# Turnout_Decoder_V1_1Hall.net
KiCad netlist of a schematic drawn in EAGLE
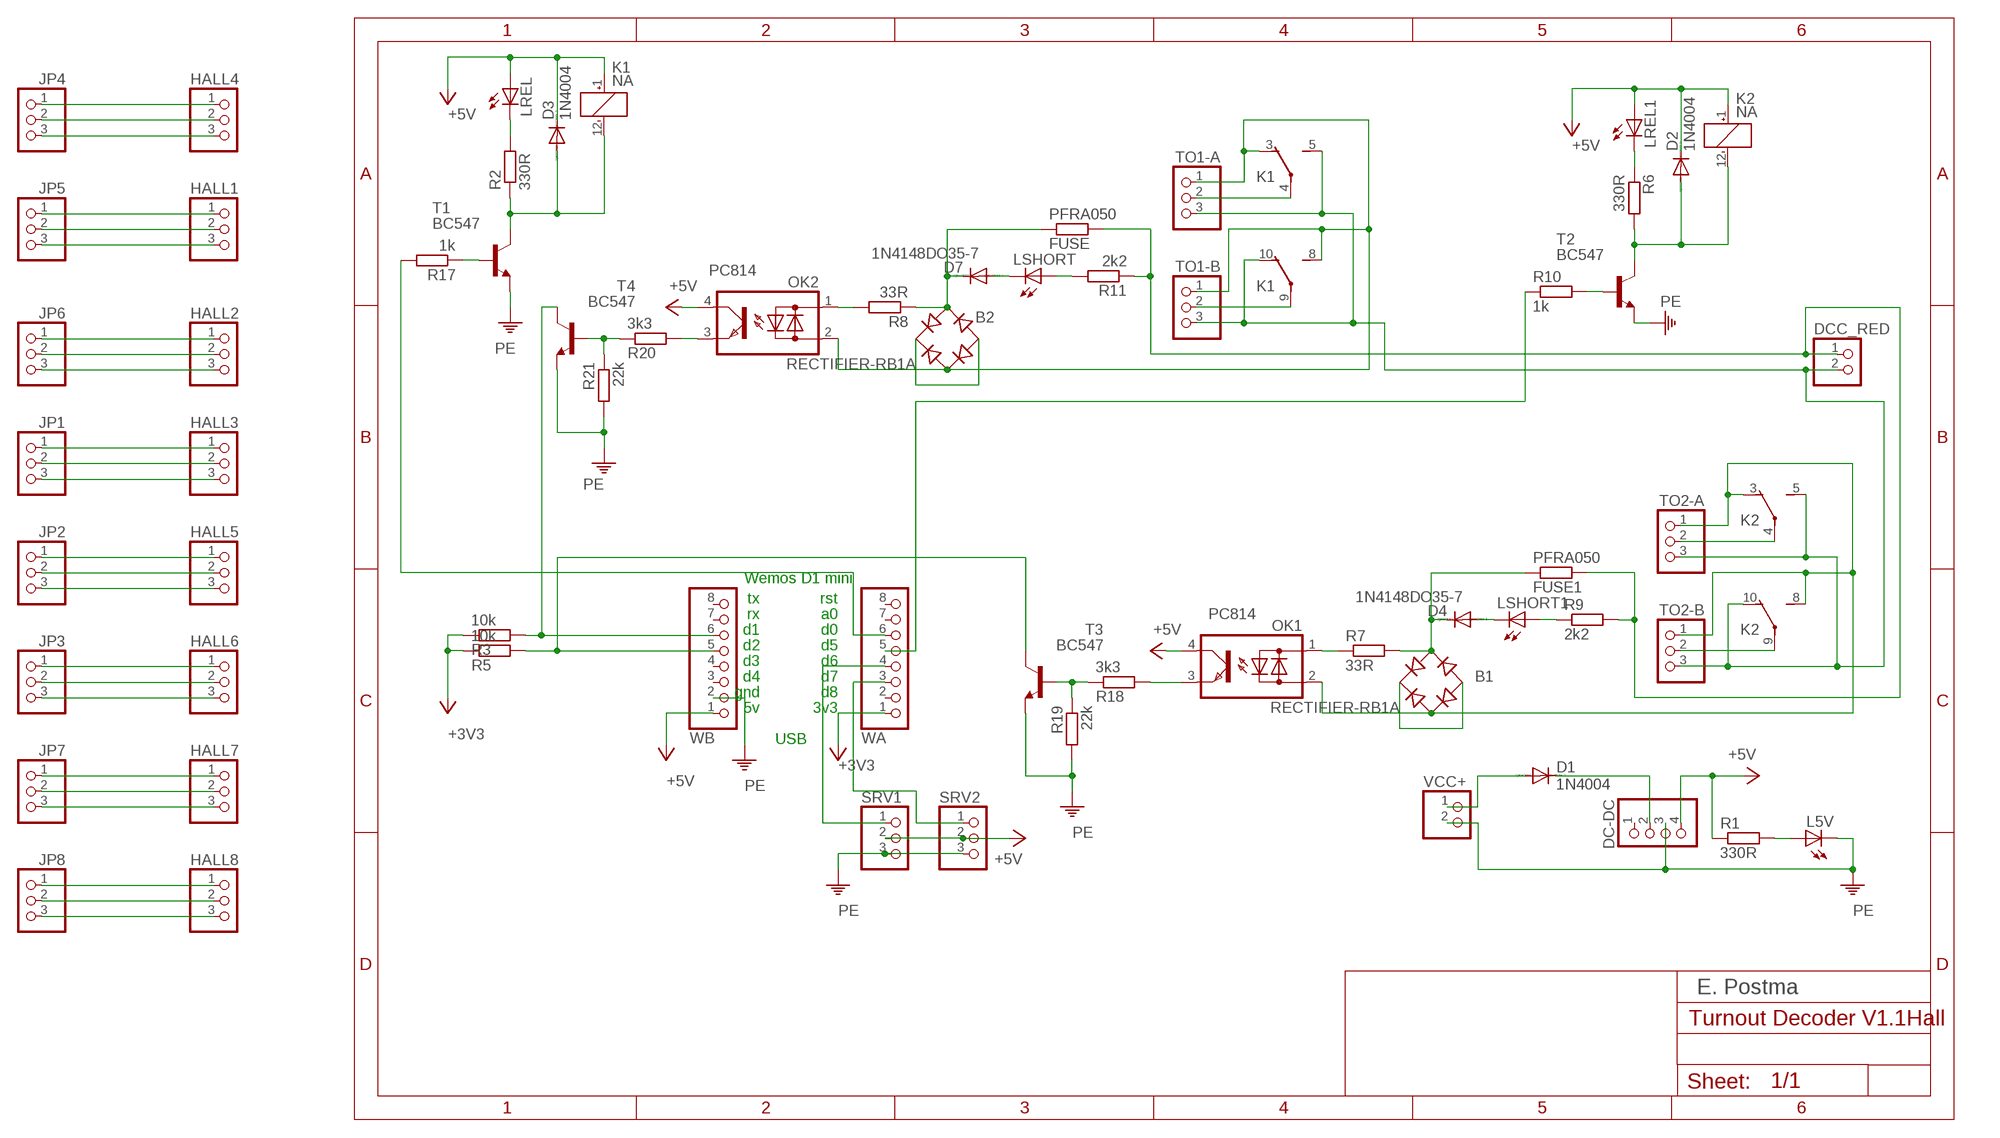
[diagram p0: schematic, sheet 1]

(export (version "E")
  (design (tool "Eeschema 10.0.6"))
  (components
    (comp (ref "B1")
      (value "RECTIFIER-RB1A")
      (footprint "eagle-import:RB1A")
      (libsource (lib "eagle-import") (part "RECTIFIER-RB1A"))
    )
    (comp (ref "B2")
      (value "RECTIFIER-RB1A")
      (footprint "eagle-import:RB1A")
      (libsource (lib "eagle-import") (part "RECTIFIER-RB1A"))
    )
    (comp (ref "D1")
      (value "1N4004")
      (footprint "eagle-import:DO41-10")
      (libsource (lib "eagle-import") (part "1N4004"))
    )
    (comp (ref "D2")
      (value "1N4004")
      (footprint "eagle-import:DO41-10")
      (libsource (lib "eagle-import") (part "1N4004"))
    )
    (comp (ref "D3")
      (value "1N4004")
      (footprint "eagle-import:DO41-10")
      (libsource (lib "eagle-import") (part "1N4004"))
    )
    (comp (ref "D4")
      (value "1N4148DO35-7")
      (footprint "eagle-import:DO35-7")
      (libsource (lib "eagle-import") (part "1N4148DO35-7"))
    )
    (comp (ref "D7")
      (value "1N4148DO35-7")
      (footprint "eagle-import:DO35-7")
      (libsource (lib "eagle-import") (part "1N4148DO35-7"))
    )
    (comp (ref "DC-DC")
      (value "PINHD-1X4")
      (footprint "eagle-import:1X04")
      (libsource (lib "eagle-import") (part "PINHD-1X4"))
    )
    (comp (ref "DCC_RED")
      (value "PINHD-1X2")
      (footprint "eagle-import:1X02")
      (libsource (lib "eagle-import") (part "PINHD-1X2"))
    )
    (comp (ref "FUSE")
      (value "PFRA050")
      (footprint "eagle-import:0414V")
      (libsource (lib "eagle-import") (part "R-EU_0414/5V"))
    )
    (comp (ref "FUSE1")
      (value "PFRA050")
      (footprint "eagle-import:0414V")
      (libsource (lib "eagle-import") (part "R-EU_0414/5V"))
    )
    (comp (ref "HALL1")
      (value "PINHD-1X3")
      (footprint "eagle-import:1X03")
      (libsource (lib "eagle-import") (part "PINHD-1X3"))
    )
    (comp (ref "HALL2")
      (value "PINHD-1X3")
      (footprint "eagle-import:1X03")
      (libsource (lib "eagle-import") (part "PINHD-1X3"))
    )
    (comp (ref "HALL3")
      (value "PINHD-1X3")
      (footprint "eagle-import:1X03")
      (libsource (lib "eagle-import") (part "PINHD-1X3"))
    )
    (comp (ref "HALL4")
      (value "PINHD-1X3")
      (footprint "eagle-import:1X03")
      (libsource (lib "eagle-import") (part "PINHD-1X3"))
    )
    (comp (ref "HALL5")
      (value "PINHD-1X3")
      (footprint "eagle-import:1X03")
      (libsource (lib "eagle-import") (part "PINHD-1X3"))
    )
    (comp (ref "HALL6")
      (value "PINHD-1X3")
      (footprint "eagle-import:1X03")
      (libsource (lib "eagle-import") (part "PINHD-1X3"))
    )
    (comp (ref "HALL7")
      (value "PINHD-1X3")
      (footprint "eagle-import:1X03")
      (libsource (lib "eagle-import") (part "PINHD-1X3"))
    )
    (comp (ref "HALL8")
      (value "PINHD-1X3")
      (footprint "eagle-import:1X03")
      (libsource (lib "eagle-import") (part "PINHD-1X3"))
    )
    (comp (ref "JP1")
      (value "PINHD-1X3")
      (footprint "eagle-import:1X03")
      (libsource (lib "eagle-import") (part "PINHD-1X3"))
    )
    (comp (ref "JP2")
      (value "PINHD-1X3")
      (footprint "eagle-import:1X03")
      (libsource (lib "eagle-import") (part "PINHD-1X3"))
    )
    (comp (ref "JP3")
      (value "PINHD-1X3")
      (footprint "eagle-import:1X03")
      (libsource (lib "eagle-import") (part "PINHD-1X3"))
    )
    (comp (ref "JP4")
      (value "PINHD-1X3")
      (footprint "eagle-import:1X03")
      (libsource (lib "eagle-import") (part "PINHD-1X3"))
    )
    (comp (ref "JP5")
      (value "PINHD-1X3")
      (footprint "eagle-import:1X03")
      (libsource (lib "eagle-import") (part "PINHD-1X3"))
    )
    (comp (ref "JP6")
      (value "PINHD-1X3")
      (footprint "eagle-import:1X03")
      (libsource (lib "eagle-import") (part "PINHD-1X3"))
    )
    (comp (ref "JP7")
      (value "PINHD-1X3")
      (footprint "eagle-import:1X03")
      (libsource (lib "eagle-import") (part "PINHD-1X3"))
    )
    (comp (ref "JP8")
      (value "PINHD-1X3")
      (footprint "eagle-import:1X03")
      (libsource (lib "eagle-import") (part "PINHD-1X3"))
    )
    (comp (ref "K1") (value "NA") (footprint "eagle-import:NA") (libsource (lib "eagle-import") (part "NA")))
    (comp (ref "K2") (value "NA") (footprint "eagle-import:NA") (libsource (lib "eagle-import") (part "NA")))
    (comp (ref "L5V")
      (value "LED3MM")
      (footprint "eagle-import:LED3MM")
      (libsource (lib "eagle-import") (part "LED3MM"))
    )
    (comp (ref "LREL")
      (value "LED3MM")
      (footprint "eagle-import:LED3MM")
      (libsource (lib "eagle-import") (part "LED3MM"))
    )
    (comp (ref "LREL1")
      (value "LED3MM")
      (footprint "eagle-import:LED3MM")
      (libsource (lib "eagle-import") (part "LED3MM"))
    )
    (comp (ref "LSHORT")
      (value "LED3MM")
      (footprint "eagle-import:LED3MM")
      (libsource (lib "eagle-import") (part "LED3MM"))
    )
    (comp (ref "LSHORT1")
      (value "LED3MM")
      (footprint "eagle-import:LED3MM")
      (libsource (lib "eagle-import") (part "LED3MM"))
    )
    (comp (ref "OK1")
      (value "PC814")
      (footprint "eagle-import:DIL04")
      (libsource (lib "eagle-import") (part "PC814"))
    )
    (comp (ref "OK2")
      (value "PC814")
      (footprint "eagle-import:DIL04")
      (libsource (lib "eagle-import") (part "PC814"))
    )
    (comp (ref "R1")
      (value "330R")
      (footprint "eagle-import:0207_7")
      (libsource (lib "eagle-import") (part "resistor_348_R-EU_0207/7"))
    )
    (comp (ref "R2")
      (value "330R")
      (footprint "eagle-import:0207_7")
      (libsource (lib "eagle-import") (part "resistor_348_R-EU_0207/7"))
    )
    (comp (ref "R3")
      (value "10k")
      (footprint "eagle-import:0207_7")
      (libsource (lib "eagle-import") (part "resistor_348_R-EU_0207/7"))
    )
    (comp (ref "R5")
      (value "10k")
      (footprint "eagle-import:0207_7")
      (libsource (lib "eagle-import") (part "resistor_348_R-EU_0207/7"))
    )
    (comp (ref "R6")
      (value "330R")
      (footprint "eagle-import:0207_7")
      (libsource (lib "eagle-import") (part "resistor_348_R-EU_0207/7"))
    )
    (comp (ref "R7")
      (value "33R")
      (footprint "eagle-import:0207_7")
      (libsource (lib "eagle-import") (part "resistor_348_R-EU_0207/7"))
    )
    (comp (ref "R8")
      (value "33R")
      (footprint "eagle-import:0207_7")
      (libsource (lib "eagle-import") (part "resistor_348_R-EU_0207/7"))
    )
    (comp (ref "R9")
      (value "2k2")
      (footprint "eagle-import:0207_7")
      (libsource (lib "eagle-import") (part "resistor_348_R-EU_0207/7"))
    )
    (comp (ref "R10")
      (value "1k")
      (footprint "eagle-import:0207_7")
      (libsource (lib "eagle-import") (part "resistor_348_R-EU_0207/7"))
    )
    (comp (ref "R11")
      (value "2k2")
      (footprint "eagle-import:0207_7")
      (libsource (lib "eagle-import") (part "resistor_348_R-EU_0207/7"))
    )
    (comp (ref "R17")
      (value "1k")
      (footprint "eagle-import:0207_7")
      (libsource (lib "eagle-import") (part "resistor_348_R-EU_0207/7"))
    )
    (comp (ref "R18")
      (value "3k3")
      (footprint "eagle-import:0207_7")
      (libsource (lib "eagle-import") (part "resistor_348_R-EU_0207/7"))
    )
    (comp (ref "R19")
      (value "22k")
      (footprint "eagle-import:0207_7")
      (libsource (lib "eagle-import") (part "resistor_348_R-EU_0207/7"))
    )
    (comp (ref "R20")
      (value "3k3")
      (footprint "eagle-import:0207_7")
      (libsource (lib "eagle-import") (part "resistor_348_R-EU_0207/7"))
    )
    (comp (ref "R21")
      (value "22k")
      (footprint "eagle-import:0207_7")
      (libsource (lib "eagle-import") (part "resistor_348_R-EU_0207/7"))
    )
    (comp (ref "SRV1")
      (value "PINHD-1X3")
      (footprint "eagle-import:1X03")
      (libsource (lib "eagle-import") (part "PINHD-1X3"))
    )
    (comp (ref "SRV2")
      (value "PINHD-1X3")
      (footprint "eagle-import:1X03")
      (libsource (lib "eagle-import") (part "PINHD-1X3"))
    )
    (comp (ref "T1")
      (value "BC547")
      (footprint "eagle-import:TO92")
      (libsource (lib "eagle-import") (part "BC547"))
    )
    (comp (ref "T2")
      (value "BC547")
      (footprint "eagle-import:TO92")
      (libsource (lib "eagle-import") (part "BC547"))
    )
    (comp (ref "T3")
      (value "BC547")
      (footprint "eagle-import:TO92")
      (libsource (lib "eagle-import") (part "BC547"))
    )
    (comp (ref "T4")
      (value "BC547")
      (footprint "eagle-import:TO92")
      (libsource (lib "eagle-import") (part "BC547"))
    )
    (comp (ref "TO1-A")
      (value "PINHD-1X3")
      (footprint "eagle-import:1X03")
      (libsource (lib "eagle-import") (part "PINHD-1X3"))
    )
    (comp (ref "TO1-B")
      (value "PINHD-1X3")
      (footprint "eagle-import:1X03")
      (libsource (lib "eagle-import") (part "PINHD-1X3"))
    )
    (comp (ref "TO2-A")
      (value "PINHD-1X3")
      (footprint "eagle-import:1X03")
      (libsource (lib "eagle-import") (part "PINHD-1X3"))
    )
    (comp (ref "TO2-B")
      (value "PINHD-1X3")
      (footprint "eagle-import:1X03")
      (libsource (lib "eagle-import") (part "PINHD-1X3"))
    )
    (comp (ref "VCC+")
      (value "PINHD-1X2")
      (footprint "eagle-import:1X02")
      (libsource (lib "eagle-import") (part "PINHD-1X2"))
    )
    (comp (ref "WA")
      (value "PINHD-1X8")
      (footprint "eagle-import:1X08")
      (libsource (lib "eagle-import") (part "PINHD-1X8"))
    )
    (comp (ref "WB")
      (value "PINHD-1X8")
      (footprint "eagle-import:1X08")
      (libsource (lib "eagle-import") (part "PINHD-1X8"))
    )
  )
  (nets
    (net (code "1") (name "+3V3") (class "Default")
      (node (ref "R3") (pin "1") (pinfunction "1_1") (pintype "passive"))
      (node (ref "R5") (pin "1") (pinfunction "1_1") (pintype "passive"))
      (node (ref "WA") (pin "1") (pinfunction "1_1") (pintype "passive"))
    )
    (net (code "2") (name "+5V") (class "Default")
      (node (ref "D2") (pin "C") (pinfunction "C_C") (pintype "passive"))
      (node (ref "D3") (pin "C") (pinfunction "C_C") (pintype "passive"))
      (node (ref "DC-DC") (pin "4") (pinfunction "4_4") (pintype "passive"))
      (node (ref "K1") (pin "1") (pinfunction "+_1") (pintype "passive"))
      (node (ref "K2") (pin "1") (pinfunction "+_1") (pintype "passive"))
      (node (ref "LREL") (pin "A") (pinfunction "A_A") (pintype "passive"))
      (node (ref "LREL1") (pin "A") (pinfunction "A_A") (pintype "passive"))
      (node (ref "OK1") (pin "4") (pinfunction "C_4") (pintype "passive"))
      (node (ref "OK2") (pin "4") (pinfunction "C_4") (pintype "passive"))
      (node (ref "R1") (pin "1") (pinfunction "1_1") (pintype "passive"))
      (node (ref "SRV1") (pin "2") (pinfunction "2_2") (pintype "passive"))
      (node (ref "SRV2") (pin "2") (pinfunction "2_2") (pintype "passive"))
      (node (ref "WB") (pin "1") (pinfunction "1_1") (pintype "passive"))
    )
    (net (code "3") (name "Net-(B1-Pad+)") (class "Default")
      (node (ref "B1") (pin "+") (pinfunction "+_+") (pintype "passive"))
      (node (ref "B1") (pin "-") (pinfunction "-_-") (pintype "passive"))
    )
    (net (code "4") (name "Net-(B1-PadAC1)") (class "Default")
      (node (ref "B1") (pin "AC1") (pinfunction "AC1_AC1") (pintype "passive"))
      (node (ref "D4") (pin "C") (pinfunction "C_C") (pintype "passive"))
      (node (ref "FUSE1") (pin "1") (pinfunction "1_1") (pintype "passive"))
      (node (ref "R7") (pin "2") (pinfunction "2_2") (pintype "passive"))
    )
    (net (code "5") (name "Net-(B2-Pad+)") (class "Default")
      (node (ref "B2") (pin "+") (pinfunction "+_+") (pintype "passive"))
      (node (ref "B2") (pin "-") (pinfunction "-_-") (pintype "passive"))
    )
    (net (code "6") (name "Net-(B2-PadAC1)") (class "Default")
      (node (ref "B2") (pin "AC1") (pinfunction "AC1_AC1") (pintype "passive"))
      (node (ref "D7") (pin "C") (pinfunction "C_C") (pintype "passive"))
      (node (ref "FUSE") (pin "1") (pinfunction "1_1") (pintype "passive"))
      (node (ref "R8") (pin "1") (pinfunction "1_1") (pintype "passive"))
    )
    (net (code "7") (name "Net-(D1-PadA)") (class "Default")
      (node (ref "D1") (pin "A") (pinfunction "A_A") (pintype "passive"))
      (node (ref "VCC+") (pin "1") (pinfunction "1_1") (pintype "passive"))
    )
    (net (code "8") (name "Net-(D1-PadC)") (class "Default")
      (node (ref "D1") (pin "C") (pinfunction "C_C") (pintype "passive"))
      (node (ref "DC-DC") (pin "2") (pinfunction "2_2") (pintype "passive"))
    )
    (net (code "9") (name "Net-(DCC_RED-Pad1)") (class "Default")
      (node (ref "DCC_RED") (pin "1") (pinfunction "1_1") (pintype "passive"))
      (node (ref "FUSE") (pin "2") (pinfunction "2_2") (pintype "passive"))
      (node (ref "FUSE1") (pin "2") (pinfunction "2_2") (pintype "passive"))
      (node (ref "R11") (pin "1") (pinfunction "1_1") (pintype "passive"))
      (node (ref "R9") (pin "2") (pinfunction "2_2") (pintype "passive"))
    )
    (net (code "10") (name "Net-(HALL1-Pad1)") (class "Default")
      (node (ref "HALL1") (pin "1") (pinfunction "1_1") (pintype "passive"))
      (node (ref "JP5") (pin "1") (pinfunction "1_1") (pintype "passive"))
    )
    (net (code "11") (name "Net-(HALL1-Pad2)") (class "Default")
      (node (ref "HALL1") (pin "2") (pinfunction "2_2") (pintype "passive"))
      (node (ref "JP5") (pin "2") (pinfunction "2_2") (pintype "passive"))
    )
    (net (code "12") (name "Net-(HALL1-Pad3)") (class "Default")
      (node (ref "HALL1") (pin "3") (pinfunction "3_3") (pintype "passive"))
      (node (ref "JP5") (pin "3") (pinfunction "3_3") (pintype "passive"))
    )
    (net (code "13") (name "Net-(HALL2-Pad1)") (class "Default")
      (node (ref "HALL2") (pin "1") (pinfunction "1_1") (pintype "passive"))
      (node (ref "JP6") (pin "1") (pinfunction "1_1") (pintype "passive"))
    )
    (net (code "14") (name "Net-(HALL2-Pad2)") (class "Default")
      (node (ref "HALL2") (pin "2") (pinfunction "2_2") (pintype "passive"))
      (node (ref "JP6") (pin "2") (pinfunction "2_2") (pintype "passive"))
    )
    (net (code "15") (name "Net-(HALL2-Pad3)") (class "Default")
      (node (ref "HALL2") (pin "3") (pinfunction "3_3") (pintype "passive"))
      (node (ref "JP6") (pin "3") (pinfunction "3_3") (pintype "passive"))
    )
    (net (code "16") (name "Net-(HALL3-Pad1)") (class "Default")
      (node (ref "HALL3") (pin "1") (pinfunction "1_1") (pintype "passive"))
      (node (ref "JP1") (pin "1") (pinfunction "1_1") (pintype "passive"))
    )
    (net (code "17") (name "Net-(HALL3-Pad2)") (class "Default")
      (node (ref "HALL3") (pin "2") (pinfunction "2_2") (pintype "passive"))
      (node (ref "JP1") (pin "2") (pinfunction "2_2") (pintype "passive"))
    )
    (net (code "18") (name "Net-(HALL3-Pad3)") (class "Default")
      (node (ref "HALL3") (pin "3") (pinfunction "3_3") (pintype "passive"))
      (node (ref "JP1") (pin "3") (pinfunction "3_3") (pintype "passive"))
    )
    (net (code "19") (name "Net-(HALL4-Pad1)") (class "Default")
      (node (ref "HALL4") (pin "1") (pinfunction "1_1") (pintype "passive"))
      (node (ref "JP4") (pin "1") (pinfunction "1_1") (pintype "passive"))
    )
    (net (code "20") (name "Net-(HALL4-Pad2)") (class "Default")
      (node (ref "HALL4") (pin "2") (pinfunction "2_2") (pintype "passive"))
      (node (ref "JP4") (pin "2") (pinfunction "2_2") (pintype "passive"))
    )
    (net (code "21") (name "Net-(HALL4-Pad3)") (class "Default")
      (node (ref "HALL4") (pin "3") (pinfunction "3_3") (pintype "passive"))
      (node (ref "JP4") (pin "3") (pinfunction "3_3") (pintype "passive"))
    )
    (net (code "22") (name "Net-(HALL5-Pad1)") (class "Default")
      (node (ref "HALL5") (pin "1") (pinfunction "1_1") (pintype "passive"))
      (node (ref "JP2") (pin "1") (pinfunction "1_1") (pintype "passive"))
    )
    (net (code "23") (name "Net-(HALL5-Pad2)") (class "Default")
      (node (ref "HALL5") (pin "2") (pinfunction "2_2") (pintype "passive"))
      (node (ref "JP2") (pin "2") (pinfunction "2_2") (pintype "passive"))
    )
    (net (code "24") (name "Net-(HALL5-Pad3)") (class "Default")
      (node (ref "HALL5") (pin "3") (pinfunction "3_3") (pintype "passive"))
      (node (ref "JP2") (pin "3") (pinfunction "3_3") (pintype "passive"))
    )
    (net (code "25") (name "Net-(HALL6-Pad1)") (class "Default")
      (node (ref "HALL6") (pin "1") (pinfunction "1_1") (pintype "passive"))
      (node (ref "JP3") (pin "1") (pinfunction "1_1") (pintype "passive"))
    )
    (net (code "26") (name "Net-(HALL6-Pad2)") (class "Default")
      (node (ref "HALL6") (pin "2") (pinfunction "2_2") (pintype "passive"))
      (node (ref "JP3") (pin "2") (pinfunction "2_2") (pintype "passive"))
    )
    (net (code "27") (name "Net-(HALL6-Pad3)") (class "Default")
      (node (ref "HALL6") (pin "3") (pinfunction "3_3") (pintype "passive"))
      (node (ref "JP3") (pin "3") (pinfunction "3_3") (pintype "passive"))
    )
    (net (code "28") (name "Net-(HALL7-Pad1)") (class "Default")
      (node (ref "HALL7") (pin "1") (pinfunction "1_1") (pintype "passive"))
      (node (ref "JP7") (pin "1") (pinfunction "1_1") (pintype "passive"))
    )
    (net (code "29") (name "Net-(HALL7-Pad2)") (class "Default")
      (node (ref "HALL7") (pin "2") (pinfunction "2_2") (pintype "passive"))
      (node (ref "JP7") (pin "2") (pinfunction "2_2") (pintype "passive"))
    )
    (net (code "30") (name "Net-(HALL7-Pad3)") (class "Default")
      (node (ref "HALL7") (pin "3") (pinfunction "3_3") (pintype "passive"))
      (node (ref "JP7") (pin "3") (pinfunction "3_3") (pintype "passive"))
    )
    (net (code "31") (name "Net-(HALL8-Pad1)") (class "Default")
      (node (ref "HALL8") (pin "1") (pinfunction "1_1") (pintype "passive"))
      (node (ref "JP8") (pin "1") (pinfunction "1_1") (pintype "passive"))
    )
    (net (code "32") (name "Net-(HALL8-Pad2)") (class "Default")
      (node (ref "HALL8") (pin "2") (pinfunction "2_2") (pintype "passive"))
      (node (ref "JP8") (pin "2") (pinfunction "2_2") (pintype "passive"))
    )
    (net (code "33") (name "Net-(HALL8-Pad3)") (class "Default")
      (node (ref "HALL8") (pin "3") (pinfunction "3_3") (pintype "passive"))
      (node (ref "JP8") (pin "3") (pinfunction "3_3") (pintype "passive"))
    )
    (net (code "34") (name "Net-(K1A--)") (class "Default")
      (node (ref "D3") (pin "A") (pinfunction "A_A") (pintype "passive"))
      (node (ref "K1") (pin "12") (pinfunction "-_12") (pintype "passive"))
      (node (ref "R2") (pin "1") (pinfunction "1_1") (pintype "passive"))
      (node (ref "T1") (pin "3") (pinfunction "C_3") (pintype "passive"))
    )
    (net (code "35") (name "Net-(K1B-O)") (class "Default")
      (node (ref "B2") (pin "AC2") (pinfunction "AC2_AC2") (pintype "passive"))
      (node (ref "K1") (pin "3") (pinfunction "O_3") (pintype "passive"))
      (node (ref "K1") (pin "8") (pinfunction "S_8") (pintype "passive"))
      (node (ref "OK2") (pin "2") (pinfunction "AC2_2") (pintype "passive"))
      (node (ref "TO1-A") (pin "1") (pinfunction "1_1") (pintype "passive"))
      (node (ref "TO1-B") (pin "1") (pinfunction "1_1") (pintype "passive"))
    )
    (net (code "36") (name "Net-(K1B-P)") (class "Default")
      (node (ref "K1") (pin "4") (pinfunction "P_4") (pintype "passive"))
      (node (ref "TO1-A") (pin "2") (pinfunction "2_2") (pintype "passive"))
    )
    (net (code "37") (name "Net-(K1B-S)") (class "Default")
      (node (ref "DCC_RED") (pin "2") (pinfunction "2_2") (pintype "passive"))
      (node (ref "K1") (pin "10") (pinfunction "O_10") (pintype "passive"))
      (node (ref "K1") (pin "5") (pinfunction "S_5") (pintype "passive"))
      (node (ref "K2") (pin "10") (pinfunction "O_10") (pintype "passive"))
      (node (ref "K2") (pin "5") (pinfunction "S_5") (pintype "passive"))
      (node (ref "TO1-A") (pin "3") (pinfunction "3_3") (pintype "passive"))
      (node (ref "TO1-B") (pin "3") (pinfunction "3_3") (pintype "passive"))
      (node (ref "TO2-A") (pin "3") (pinfunction "3_3") (pintype "passive"))
      (node (ref "TO2-B") (pin "3") (pinfunction "3_3") (pintype "passive"))
    )
    (net (code "38") (name "Net-(K1C-P)") (class "Default")
      (node (ref "K1") (pin "9") (pinfunction "P_9") (pintype "passive"))
      (node (ref "TO1-B") (pin "2") (pinfunction "2_2") (pintype "passive"))
    )
    (net (code "39") (name "Net-(K2A--)") (class "Default")
      (node (ref "D2") (pin "A") (pinfunction "A_A") (pintype "passive"))
      (node (ref "K2") (pin "12") (pinfunction "-_12") (pintype "passive"))
      (node (ref "R6") (pin "2") (pinfunction "2_2") (pintype "passive"))
      (node (ref "T2") (pin "3") (pinfunction "C_3") (pintype "passive"))
    )
    (net (code "40") (name "Net-(K2B-O)") (class "Default")
      (node (ref "B1") (pin "AC2") (pinfunction "AC2_AC2") (pintype "passive"))
      (node (ref "K2") (pin "3") (pinfunction "O_3") (pintype "passive"))
      (node (ref "K2") (pin "8") (pinfunction "S_8") (pintype "passive"))
      (node (ref "OK1") (pin "2") (pinfunction "AC2_2") (pintype "passive"))
      (node (ref "TO2-A") (pin "1") (pinfunction "1_1") (pintype "passive"))
      (node (ref "TO2-B") (pin "1") (pinfunction "1_1") (pintype "passive"))
    )
    (net (code "41") (name "Net-(K2B-P)") (class "Default")
      (node (ref "K2") (pin "4") (pinfunction "P_4") (pintype "passive"))
      (node (ref "TO2-A") (pin "2") (pinfunction "2_2") (pintype "passive"))
    )
    (net (code "42") (name "Net-(K2C-P)") (class "Default")
      (node (ref "K2") (pin "9") (pinfunction "P_9") (pintype "passive"))
      (node (ref "TO2-B") (pin "2") (pinfunction "2_2") (pintype "passive"))
    )
    (net (code "43") (name "Net-(L5V-PadA)") (class "Default")
      (node (ref "L5V") (pin "A") (pinfunction "A_A") (pintype "passive"))
      (node (ref "R1") (pin "2") (pinfunction "2_2") (pintype "passive"))
    )
    (net (code "44") (name "Net-(LREL-C)") (class "Default")
      (node (ref "LREL") (pin "K") (pinfunction "C_K") (pintype "passive"))
      (node (ref "R2") (pin "2") (pinfunction "2_2") (pintype "passive"))
    )
    (net (code "45") (name "Net-(LREL1-C)") (class "Default")
      (node (ref "LREL1") (pin "K") (pinfunction "C_K") (pintype "passive"))
      (node (ref "R6") (pin "1") (pinfunction "1_1") (pintype "passive"))
    )
    (net (code "46") (name "Net-(LSHORT-C)") (class "Default")
      (node (ref "D7") (pin "A") (pinfunction "A_A") (pintype "passive"))
      (node (ref "LSHORT") (pin "K") (pinfunction "C_K") (pintype "passive"))
    )
    (net (code "47") (name "Net-(LSHORT-PadA)") (class "Default")
      (node (ref "LSHORT") (pin "A") (pinfunction "A_A") (pintype "passive"))
      (node (ref "R11") (pin "2") (pinfunction "2_2") (pintype "passive"))
    )
    (net (code "48") (name "Net-(LSHORT1-C)") (class "Default")
      (node (ref "D4") (pin "A") (pinfunction "A_A") (pintype "passive"))
      (node (ref "LSHORT1") (pin "K") (pinfunction "C_K") (pintype "passive"))
    )
    (net (code "49") (name "Net-(LSHORT1-PadA)") (class "Default")
      (node (ref "LSHORT1") (pin "A") (pinfunction "A_A") (pintype "passive"))
      (node (ref "R9") (pin "1") (pinfunction "1_1") (pintype "passive"))
    )
    (net (code "50") (name "Net-(OK1-AC1)") (class "Default")
      (node (ref "OK1") (pin "1") (pinfunction "AC1_1") (pintype "passive"))
      (node (ref "R7") (pin "1") (pinfunction "1_1") (pintype "passive"))
    )
    (net (code "51") (name "Net-(OK1-E)") (class "Default")
      (node (ref "OK1") (pin "3") (pinfunction "E_3") (pintype "passive"))
      (node (ref "R18") (pin "2") (pinfunction "2_2") (pintype "passive"))
    )
    (net (code "52") (name "Net-(OK2-AC1)") (class "Default")
      (node (ref "OK2") (pin "1") (pinfunction "AC1_1") (pintype "passive"))
      (node (ref "R8") (pin "2") (pinfunction "2_2") (pintype "passive"))
    )
    (net (code "53") (name "Net-(OK2-E)") (class "Default")
      (node (ref "OK2") (pin "3") (pinfunction "E_3") (pintype "passive"))
      (node (ref "R20") (pin "2") (pinfunction "2_2") (pintype "passive"))
    )
    (net (code "54") (name "Net-(R10-Pad1)") (class "Default")
      (node (ref "R10") (pin "1") (pinfunction "1_1") (pintype "passive"))
      (node (ref "WA") (pin "5") (pinfunction "5_5") (pintype "passive"))
    )
    (net (code "55") (name "Net-(R17-Pad2)") (class "Default")
      (node (ref "R17") (pin "2") (pinfunction "2_2") (pintype "passive"))
      (node (ref "WA") (pin "6") (pinfunction "6_6") (pintype "passive"))
    )
    (net (code "56") (name "Net-(SRV1-Pad1)") (class "Default")
      (node (ref "SRV1") (pin "1") (pinfunction "1_1") (pintype "passive"))
      (node (ref "WA") (pin "4") (pinfunction "4_4") (pintype "passive"))
    )
    (net (code "57") (name "Net-(SRV2-Pad1)") (class "Default")
      (node (ref "SRV2") (pin "1") (pinfunction "1_1") (pintype "passive"))
      (node (ref "WA") (pin "3") (pinfunction "3_3") (pintype "passive"))
    )
    (net (code "58") (name "Net-(T1-B)") (class "Default")
      (node (ref "R17") (pin "1") (pinfunction "1_1") (pintype "passive"))
      (node (ref "T1") (pin "2") (pinfunction "B_2") (pintype "passive"))
    )
    (net (code "59") (name "Net-(T2-B)") (class "Default")
      (node (ref "R10") (pin "2") (pinfunction "2_2") (pintype "passive"))
      (node (ref "T2") (pin "2") (pinfunction "B_2") (pintype "passive"))
    )
    (net (code "60") (name "Net-(T3-B)") (class "Default")
      (node (ref "R18") (pin "1") (pinfunction "1_1") (pintype "passive"))
      (node (ref "R19") (pin "1") (pinfunction "1_1") (pintype "passive"))
      (node (ref "T3") (pin "2") (pinfunction "B_2") (pintype "passive"))
    )
    (net (code "61") (name "Net-(T3-C)") (class "Default")
      (node (ref "R5") (pin "2") (pinfunction "2_2") (pintype "passive"))
      (node (ref "T3") (pin "3") (pinfunction "C_3") (pintype "passive"))
      (node (ref "WB") (pin "5") (pinfunction "5_5") (pintype "passive"))
    )
    (net (code "62") (name "Net-(T4-B)") (class "Default")
      (node (ref "R20") (pin "1") (pinfunction "1_1") (pintype "passive"))
      (node (ref "R21") (pin "1") (pinfunction "1_1") (pintype "passive"))
      (node (ref "T4") (pin "2") (pinfunction "B_2") (pintype "passive"))
    )
    (net (code "63") (name "Net-(T4-C)") (class "Default")
      (node (ref "R3") (pin "2") (pinfunction "2_2") (pintype "passive"))
      (node (ref "T4") (pin "3") (pinfunction "C_3") (pintype "passive"))
      (node (ref "WB") (pin "6") (pinfunction "6_6") (pintype "passive"))
    )
    (net (code "64") (name "PE") (class "Default")
      (node (ref "DC-DC") (pin "3") (pinfunction "3_3") (pintype "passive"))
      (node (ref "L5V") (pin "K") (pinfunction "C_K") (pintype "passive"))
      (node (ref "R19") (pin "2") (pinfunction "2_2") (pintype "passive"))
      (node (ref "R21") (pin "2") (pinfunction "2_2") (pintype "passive"))
      (node (ref "SRV1") (pin "3") (pinfunction "3_3") (pintype "passive"))
      (node (ref "SRV2") (pin "3") (pinfunction "3_3") (pintype "passive"))
      (node (ref "T1") (pin "1") (pinfunction "E_1") (pintype "passive"))
      (node (ref "T2") (pin "1") (pinfunction "E_1") (pintype "passive"))
      (node (ref "T3") (pin "1") (pinfunction "E_1") (pintype "passive"))
      (node (ref "T4") (pin "1") (pinfunction "E_1") (pintype "passive"))
      (node (ref "VCC+") (pin "2") (pinfunction "2_2") (pintype "passive"))
      (node (ref "WB") (pin "2") (pinfunction "2_2") (pintype "passive"))
    )
    (net (code "65") (name "unconnected-(DC-DC-Pad1)") (class "Default")
      (node (ref "DC-DC") (pin "1") (pinfunction "1_1") (pintype "passive"))
    )
    (net (code "66") (name "unconnected-(WA-Pad2)") (class "Default")
      (node (ref "WA") (pin "2") (pinfunction "2_2") (pintype "passive"))
    )
    (net (code "67") (name "unconnected-(WA-Pad7)") (class "Default")
      (node (ref "WA") (pin "7") (pinfunction "7_7") (pintype "passive"))
    )
    (net (code "68") (name "unconnected-(WA-Pad8)") (class "Default")
      (node (ref "WA") (pin "8") (pinfunction "8_8") (pintype "passive"))
    )
    (net (code "69") (name "unconnected-(WB-Pad3)") (class "Default")
      (node (ref "WB") (pin "3") (pinfunction "3_3") (pintype "passive"))
    )
    (net (code "70") (name "unconnected-(WB-Pad4)") (class "Default")
      (node (ref "WB") (pin "4") (pinfunction "4_4") (pintype "passive"))
    )
    (net (code "71") (name "unconnected-(WB-Pad7)") (class "Default")
      (node (ref "WB") (pin "7") (pinfunction "7_7") (pintype "passive"))
    )
    (net (code "72") (name "unconnected-(WB-Pad8)") (class "Default")
      (node (ref "WB") (pin "8") (pinfunction "8_8") (pintype "passive"))
    )
  )
)
